# relay-shield.net
KiCad netlist of a schematic drawn in EAGLE
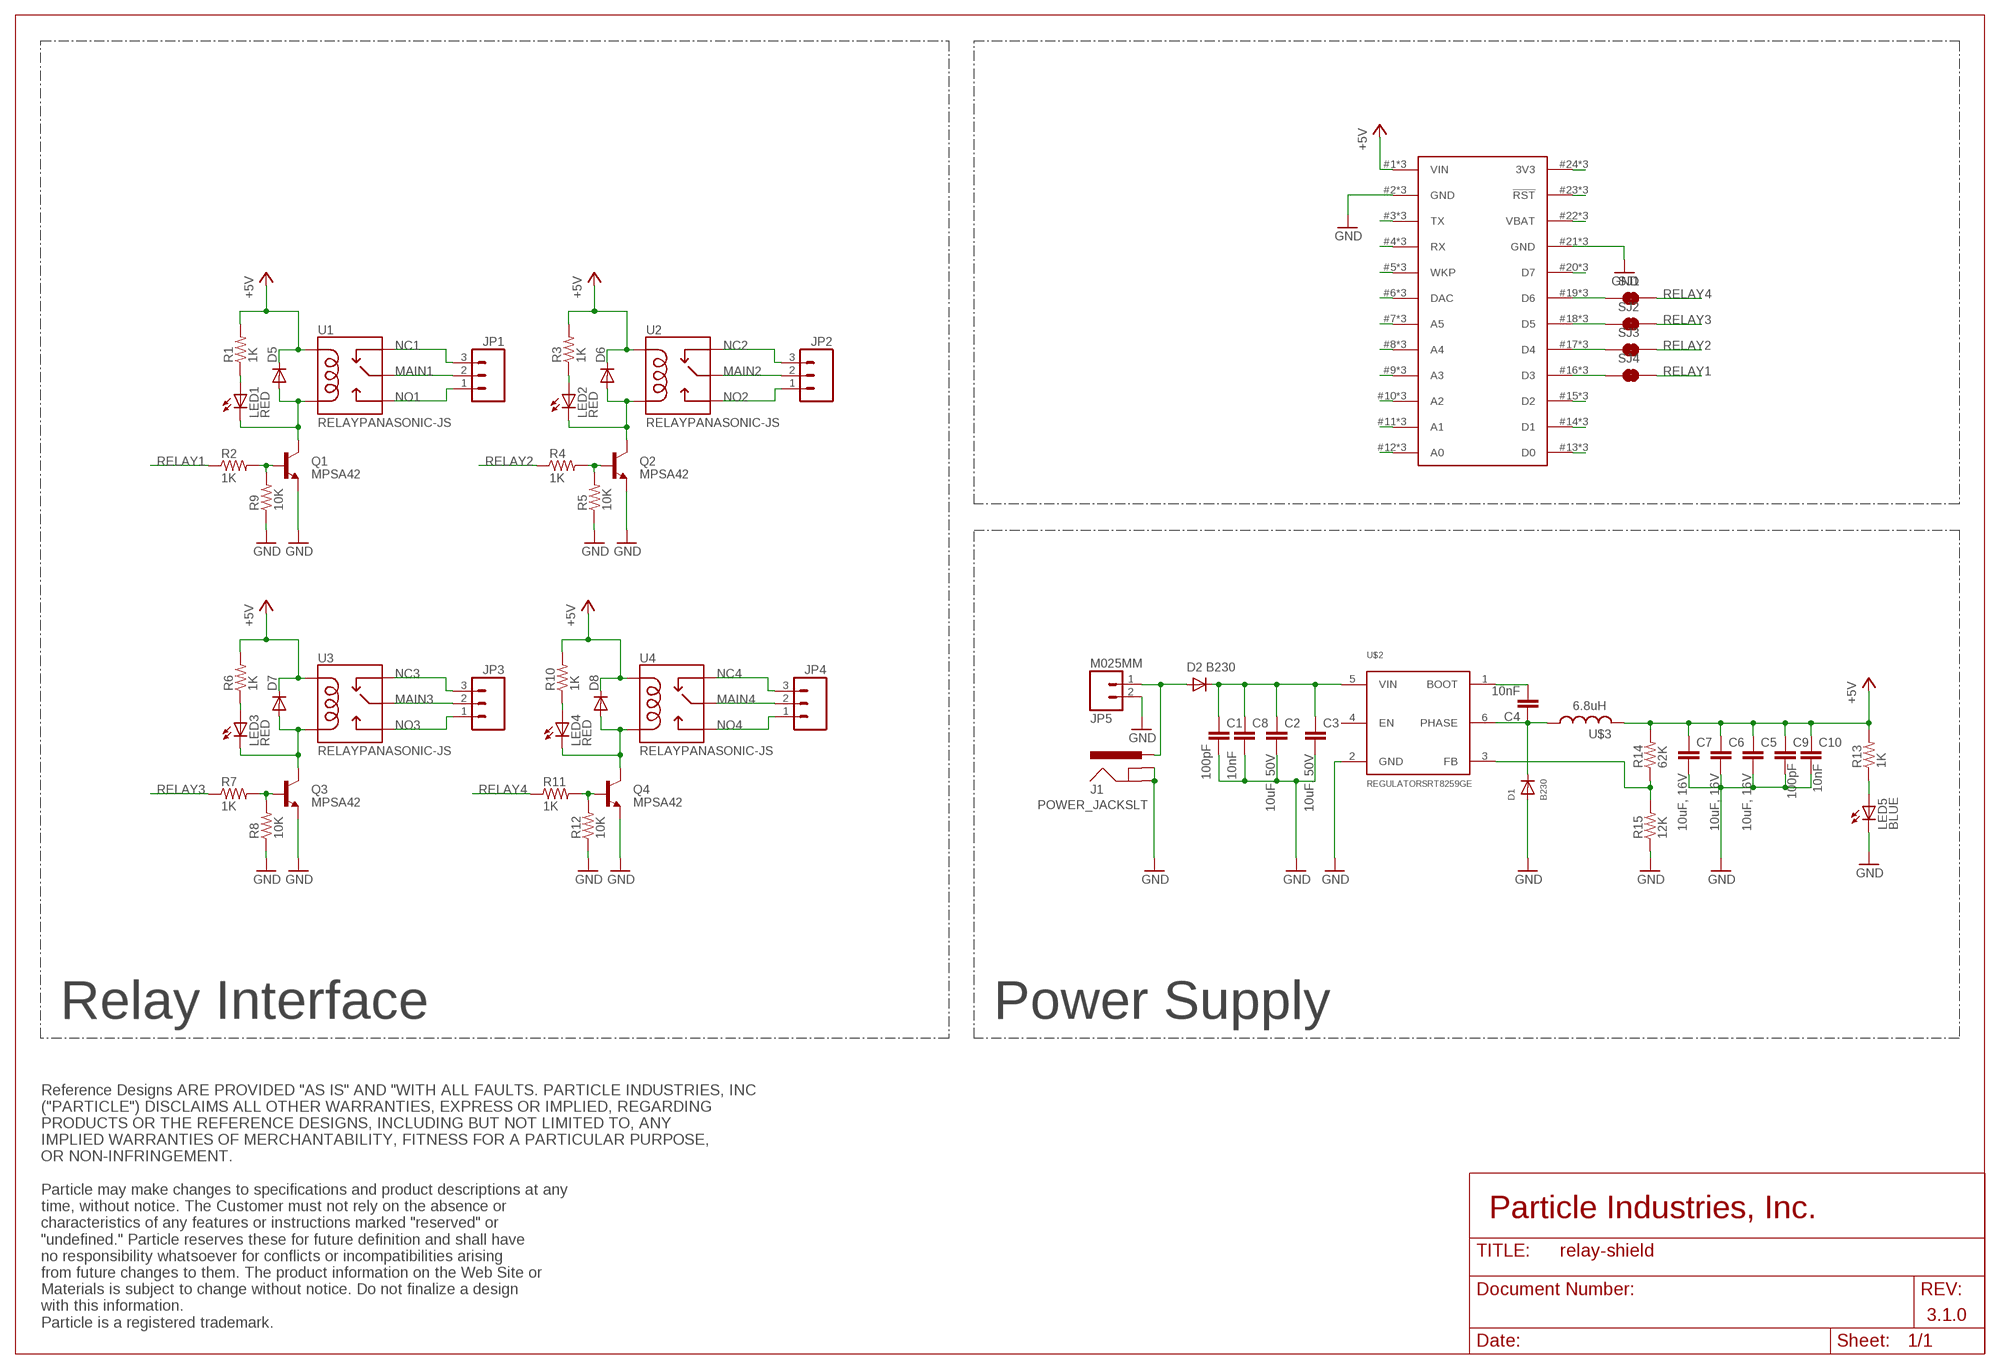
[diagram p0: schematic, sheet 1]

(export (version "E")
  (design (tool "Eeschema 10.0.6"))
  (components
    (comp (ref "C1")
      (value "100pF")
      (footprint "eagle-import:C0603")
      (libsource (lib "eagle-import") (part "C-EUC0603"))
    )
    (comp (ref "C2")
      (value "10uF, 50V")
      (footprint "eagle-import:1206")
      (libsource (lib "eagle-import") (part "CAP1206"))
    )
    (comp (ref "C3")
      (value "10uF, 50V")
      (footprint "eagle-import:1206")
      (libsource (lib "eagle-import") (part "CAP1206"))
    )
    (comp (ref "C4")
      (value "10nF")
      (footprint "eagle-import:0603-CAP")
      (libsource (lib "eagle-import") (part "CAP0603-CAP"))
    )
    (comp (ref "C5")
      (value "10uF, 16V")
      (footprint "eagle-import:1206")
      (libsource (lib "eagle-import") (part "CAP1206"))
    )
    (comp (ref "C6")
      (value "10uF, 16V")
      (footprint "eagle-import:1206")
      (libsource (lib "eagle-import") (part "CAP1206"))
    )
    (comp (ref "C7")
      (value "10uF, 16V")
      (footprint "eagle-import:1206")
      (libsource (lib "eagle-import") (part "CAP1206"))
    )
    (comp (ref "C8")
      (value "10nF")
      (footprint "eagle-import:C0603")
      (libsource (lib "eagle-import") (part "C-EUC0603"))
    )
    (comp (ref "C9")
      (value "100pF")
      (footprint "eagle-import:C0603")
      (libsource (lib "eagle-import") (part "C-EUC0603"))
    )
    (comp (ref "C10")
      (value "10nF")
      (footprint "eagle-import:C0603")
      (libsource (lib "eagle-import") (part "C-EUC0603"))
    )
    (comp (ref "D1")
      (value "B230")
      (footprint "eagle-import:SMADIODE")
      (libsource (lib "eagle-import") (part "DIODESMA"))
    )
    (comp (ref "D2")
      (value "B230")
      (footprint "eagle-import:SMADIODE")
      (libsource (lib "eagle-import") (part "DIODESMA"))
    )
    (comp (ref "D5")
      (value "DIODE-SOD123")
      (footprint "eagle-import:SOD123")
      (libsource (lib "eagle-import") (part "DIODE-SOD123"))
    )
    (comp (ref "D6")
      (value "DIODE-SOD123")
      (footprint "eagle-import:SOD123")
      (libsource (lib "eagle-import") (part "DIODE-SOD123"))
    )
    (comp (ref "D7")
      (value "DIODE-SOD123")
      (footprint "eagle-import:SOD123")
      (libsource (lib "eagle-import") (part "DIODE-SOD123"))
    )
    (comp (ref "D8")
      (value "DIODE-SOD123")
      (footprint "eagle-import:SOD123")
      (libsource (lib "eagle-import") (part "DIODE-SOD123"))
    )
    (comp (ref "J1")
      (value "POWER_JACKSLT")
      (footprint "eagle-import:POWER_JACK_SLOT")
      (libsource (lib "eagle-import") (part "POWER_JACKSLT"))
    )
    (comp (ref "JP1")
      (value "M03-SCREW-5MM")
      (footprint "eagle-import:SCREWTERMINAL-5MM-3")
      (libsource (lib "eagle-import") (part "M03-SCREW-5MM"))
    )
    (comp (ref "JP2")
      (value "M03-SCREW-5MM")
      (footprint "eagle-import:SCREWTERMINAL-5MM-3")
      (libsource (lib "eagle-import") (part "M03-SCREW-5MM"))
    )
    (comp (ref "JP3")
      (value "M03-SCREW-5MM")
      (footprint "eagle-import:SCREWTERMINAL-5MM-3")
      (libsource (lib "eagle-import") (part "M03-SCREW-5MM"))
    )
    (comp (ref "JP4")
      (value "M03-SCREW-5MM")
      (footprint "eagle-import:SCREWTERMINAL-5MM-3")
      (libsource (lib "eagle-import") (part "M03-SCREW-5MM"))
    )
    (comp (ref "JP5")
      (value "M025MM")
      (footprint "eagle-import:SCREWTERMINAL-5MM-2")
      (libsource (lib "eagle-import") (part "M025MM"))
    )
    (comp (ref "LED1")
      (value "RED")
      (footprint "eagle-import:LED-0603")
      (libsource (lib "eagle-import") (part "LED0603"))
    )
    (comp (ref "LED2")
      (value "RED")
      (footprint "eagle-import:LED-0603")
      (libsource (lib "eagle-import") (part "LED0603"))
    )
    (comp (ref "LED3")
      (value "RED")
      (footprint "eagle-import:LED-0603")
      (libsource (lib "eagle-import") (part "LED0603"))
    )
    (comp (ref "LED4")
      (value "RED")
      (footprint "eagle-import:LED-0603")
      (libsource (lib "eagle-import") (part "LED0603"))
    )
    (comp (ref "LED5")
      (value "BLUE")
      (footprint "eagle-import:LED-0603")
      (libsource (lib "eagle-import") (part "LED0603"))
    )
    (comp (ref "Q1")
      (value "MPSA42")
      (footprint "eagle-import:SOT23")
      (libsource (lib "eagle-import") (part "TRANSISTOR_NPNMPSA42"))
    )
    (comp (ref "Q2")
      (value "MPSA42")
      (footprint "eagle-import:SOT23")
      (libsource (lib "eagle-import") (part "TRANSISTOR_NPNMPSA42"))
    )
    (comp (ref "Q3")
      (value "MPSA42")
      (footprint "eagle-import:SOT23")
      (libsource (lib "eagle-import") (part "TRANSISTOR_NPNMPSA42"))
    )
    (comp (ref "Q4")
      (value "MPSA42")
      (footprint "eagle-import:SOT23")
      (libsource (lib "eagle-import") (part "TRANSISTOR_NPNMPSA42"))
    )
    (comp (ref "R1")
      (value "1K")
      (footprint "eagle-import:0603-RES")
      (libsource (lib "eagle-import") (part "RESISTOR0603-RES"))
    )
    (comp (ref "R2")
      (value "1K")
      (footprint "eagle-import:0603-RES")
      (libsource (lib "eagle-import") (part "RESISTOR0603-RES"))
    )
    (comp (ref "R3")
      (value "1K")
      (footprint "eagle-import:0603-RES")
      (libsource (lib "eagle-import") (part "RESISTOR0603-RES"))
    )
    (comp (ref "R4")
      (value "1K")
      (footprint "eagle-import:0603-RES")
      (libsource (lib "eagle-import") (part "RESISTOR0603-RES"))
    )
    (comp (ref "R5")
      (value "10K")
      (footprint "eagle-import:0603-RES")
      (libsource (lib "eagle-import") (part "RESISTOR0603-RES"))
    )
    (comp (ref "R6")
      (value "1K")
      (footprint "eagle-import:0603-RES")
      (libsource (lib "eagle-import") (part "RESISTOR0603-RES"))
    )
    (comp (ref "R7")
      (value "1K")
      (footprint "eagle-import:0603-RES")
      (libsource (lib "eagle-import") (part "RESISTOR0603-RES"))
    )
    (comp (ref "R8")
      (value "10K")
      (footprint "eagle-import:0603-RES")
      (libsource (lib "eagle-import") (part "RESISTOR0603-RES"))
    )
    (comp (ref "R9")
      (value "10K")
      (footprint "eagle-import:0603-RES")
      (libsource (lib "eagle-import") (part "RESISTOR0603-RES"))
    )
    (comp (ref "R10")
      (value "1K")
      (footprint "eagle-import:0603-RES")
      (libsource (lib "eagle-import") (part "RESISTOR0603-RES"))
    )
    (comp (ref "R11")
      (value "1K")
      (footprint "eagle-import:0603-RES")
      (libsource (lib "eagle-import") (part "RESISTOR0603-RES"))
    )
    (comp (ref "R12")
      (value "10K")
      (footprint "eagle-import:0603-RES")
      (libsource (lib "eagle-import") (part "RESISTOR0603-RES"))
    )
    (comp (ref "R13")
      (value "1K")
      (footprint "eagle-import:0603-RES")
      (libsource (lib "eagle-import") (part "RESISTOR0603-RES"))
    )
    (comp (ref "R14")
      (value "62K")
      (footprint "eagle-import:0603-RES")
      (libsource (lib "eagle-import") (part "RESISTOR0603-RES"))
    )
    (comp (ref "R15")
      (value "12K")
      (footprint "eagle-import:0603-RES")
      (libsource (lib "eagle-import") (part "RESISTOR0603-RES"))
    )
    (comp (ref "SJ1")
      (value "JUMPER-PAD-2-NC_BY_TRACE")
      (footprint "eagle-import:PAD-JUMPER-2-NC_BY_TRACE_YES_SILK")
      (libsource (lib "eagle-import") (part "JUMPER-PAD-2-NC_BY_TRACE"))
    )
    (comp (ref "SJ2")
      (value "JUMPER-PAD-2-NC_BY_TRACE")
      (footprint "eagle-import:PAD-JUMPER-2-NC_BY_TRACE_YES_SILK")
      (libsource (lib "eagle-import") (part "JUMPER-PAD-2-NC_BY_TRACE"))
    )
    (comp (ref "SJ3")
      (value "JUMPER-PAD-2-NC_BY_TRACE")
      (footprint "eagle-import:PAD-JUMPER-2-NC_BY_TRACE_YES_SILK")
      (libsource (lib "eagle-import") (part "JUMPER-PAD-2-NC_BY_TRACE"))
    )
    (comp (ref "SJ4")
      (value "JUMPER-PAD-2-NC_BY_TRACE")
      (footprint "eagle-import:PAD-JUMPER-2-NC_BY_TRACE_YES_SILK")
      (libsource (lib "eagle-import") (part "JUMPER-PAD-2-NC_BY_TRACE"))
    )
    (comp (ref "U$1")
      (value "SPARK_CORESTACKABLE")
      (footprint "eagle-import:SPARK_CORE_STACKABLE")
      (libsource (lib "eagle-import") (part "SPARK_CORESTACKABLE"))
    )
    (comp (ref "U$2")
      (value "REGULATORSRT8259GE")
      (footprint "eagle-import:SOT23-6")
      (libsource (lib "eagle-import") (part "REGULATORSRT8259GE"))
    )
    (comp (ref "U$3")
      (value "INDUCTORS")
      (footprint "eagle-import:NR8040T6R8N")
      (libsource (lib "eagle-import") (part "INDUCTORS"))
    )
    (comp (ref "U1")
      (value "RELAYPANASONIC-JS")
      (footprint "eagle-import:JS1-5V-F")
      (libsource (lib "eagle-import") (part "RELAYPANASONIC-JS"))
    )
    (comp (ref "U2")
      (value "RELAYPANASONIC-JS")
      (footprint "eagle-import:JS1-5V-F")
      (libsource (lib "eagle-import") (part "RELAYPANASONIC-JS"))
    )
    (comp (ref "U3")
      (value "RELAYPANASONIC-JS")
      (footprint "eagle-import:JS1-5V-F")
      (libsource (lib "eagle-import") (part "RELAYPANASONIC-JS"))
    )
    (comp (ref "U4")
      (value "RELAYPANASONIC-JS")
      (footprint "eagle-import:JS1-5V-F")
      (libsource (lib "eagle-import") (part "RELAYPANASONIC-JS"))
    )
  )
  (nets
    (net (code "1") (name "+5V") (class "Default")
      (node (ref "C10") (pin "1") (pinfunction "1_1") (pintype "passive"))
      (node (ref "C5") (pin "1") (pinfunction "1_1") (pintype "passive"))
      (node (ref "C6") (pin "1") (pinfunction "1_1") (pintype "passive"))
      (node (ref "C7") (pin "1") (pinfunction "1_1") (pintype "passive"))
      (node (ref "C9") (pin "1") (pinfunction "1_1") (pintype "passive"))
      (node (ref "D5") (pin "C") (pinfunction "C_C") (pintype "passive"))
      (node (ref "D6") (pin "C") (pinfunction "C_C") (pintype "passive"))
      (node (ref "D7") (pin "C") (pinfunction "C_C") (pintype "passive"))
      (node (ref "D8") (pin "C") (pinfunction "C_C") (pintype "passive"))
      (node (ref "R1") (pin "2") (pinfunction "2_2") (pintype "passive"))
      (node (ref "R10") (pin "2") (pinfunction "2_2") (pintype "passive"))
      (node (ref "R13") (pin "2") (pinfunction "2_2") (pintype "passive"))
      (node (ref "R14") (pin "2") (pinfunction "2_2") (pintype "passive"))
      (node (ref "R3") (pin "2") (pinfunction "2_2") (pintype "passive"))
      (node (ref "R6") (pin "2") (pinfunction "2_2") (pintype "passive"))
      (node (ref "U$1") (pin "#1") (pinfunction "VIN_#1") (pintype "power_in"))
      (node (ref "U$1") (pin "1") (pinfunction "VIN_1") (pintype "power_in"))
      (node (ref "U$1") (pin "@1") (pinfunction "VIN_@1") (pintype "power_in"))
      (node (ref "U$3") (pin "P$2") (pinfunction "2_P$2") (pintype "passive"))
      (node (ref "U1") (pin "COIL1") (pinfunction "COIL1_COIL1") (pintype "bidirectional"))
      (node (ref "U2") (pin "COIL1") (pinfunction "COIL1_COIL1") (pintype "bidirectional"))
      (node (ref "U3") (pin "COIL1") (pinfunction "COIL1_COIL1") (pintype "bidirectional"))
      (node (ref "U4") (pin "COIL1") (pinfunction "COIL1_COIL1") (pintype "bidirectional"))
    )
    (net (code "2") (name "/MAIN1") (class "Default")
      (node (ref "JP1") (pin "2") (pinfunction "2_2") (pintype "passive"))
      (node (ref "U1") (pin "COMMON") (pinfunction "MAIN_COMMON") (pintype "bidirectional"))
    )
    (net (code "3") (name "/MAIN2") (class "Default")
      (node (ref "JP2") (pin "2") (pinfunction "2_2") (pintype "passive"))
      (node (ref "U2") (pin "COMMON") (pinfunction "MAIN_COMMON") (pintype "bidirectional"))
    )
    (net (code "4") (name "/MAIN3") (class "Default")
      (node (ref "JP3") (pin "2") (pinfunction "2_2") (pintype "passive"))
      (node (ref "U3") (pin "COMMON") (pinfunction "MAIN_COMMON") (pintype "bidirectional"))
    )
    (net (code "5") (name "/MAIN4") (class "Default")
      (node (ref "JP4") (pin "2") (pinfunction "2_2") (pintype "passive"))
      (node (ref "U4") (pin "COMMON") (pinfunction "MAIN_COMMON") (pintype "bidirectional"))
    )
    (net (code "6") (name "/NC1") (class "Default")
      (node (ref "JP1") (pin "3") (pinfunction "3_3") (pintype "passive"))
      (node (ref "U1") (pin "CLOSED") (pinfunction "NC_CLOSED") (pintype "bidirectional"))
    )
    (net (code "7") (name "/NC2") (class "Default")
      (node (ref "JP2") (pin "3") (pinfunction "3_3") (pintype "passive"))
      (node (ref "U2") (pin "CLOSED") (pinfunction "NC_CLOSED") (pintype "bidirectional"))
    )
    (net (code "8") (name "/NC3") (class "Default")
      (node (ref "JP3") (pin "3") (pinfunction "3_3") (pintype "passive"))
      (node (ref "U3") (pin "CLOSED") (pinfunction "NC_CLOSED") (pintype "bidirectional"))
    )
    (net (code "9") (name "/NC4") (class "Default")
      (node (ref "JP4") (pin "3") (pinfunction "3_3") (pintype "passive"))
      (node (ref "U4") (pin "CLOSED") (pinfunction "NC_CLOSED") (pintype "bidirectional"))
    )
    (net (code "10") (name "/NO1") (class "Default")
      (node (ref "JP1") (pin "1") (pinfunction "1_1") (pintype "passive"))
      (node (ref "U1") (pin "OPEN") (pinfunction "NO_OPEN") (pintype "bidirectional"))
    )
    (net (code "11") (name "/NO2") (class "Default")
      (node (ref "JP2") (pin "1") (pinfunction "1_1") (pintype "passive"))
      (node (ref "U2") (pin "OPEN") (pinfunction "NO_OPEN") (pintype "bidirectional"))
    )
    (net (code "12") (name "/NO3") (class "Default")
      (node (ref "JP3") (pin "1") (pinfunction "1_1") (pintype "passive"))
      (node (ref "U3") (pin "OPEN") (pinfunction "NO_OPEN") (pintype "bidirectional"))
    )
    (net (code "13") (name "/NO4") (class "Default")
      (node (ref "JP4") (pin "1") (pinfunction "1_1") (pintype "passive"))
      (node (ref "U4") (pin "OPEN") (pinfunction "NO_OPEN") (pintype "bidirectional"))
    )
    (net (code "14") (name "/RELAY1") (class "Default")
      (node (ref "R2") (pin "1") (pinfunction "1_1") (pintype "passive"))
      (node (ref "SJ4") (pin "2") (pinfunction "2_2") (pintype "passive"))
    )
    (net (code "15") (name "/RELAY2") (class "Default")
      (node (ref "R4") (pin "1") (pinfunction "1_1") (pintype "passive"))
      (node (ref "SJ3") (pin "2") (pinfunction "2_2") (pintype "passive"))
    )
    (net (code "16") (name "/RELAY3") (class "Default")
      (node (ref "R7") (pin "1") (pinfunction "1_1") (pintype "passive"))
      (node (ref "SJ2") (pin "2") (pinfunction "2_2") (pintype "passive"))
    )
    (net (code "17") (name "/RELAY4") (class "Default")
      (node (ref "R11") (pin "1") (pinfunction "1_1") (pintype "passive"))
      (node (ref "SJ1") (pin "2") (pinfunction "2_2") (pintype "passive"))
    )
    (net (code "18") (name "GND") (class "Default")
      (node (ref "C1") (pin "2") (pinfunction "2_2") (pintype "passive"))
      (node (ref "C10") (pin "2") (pinfunction "2_2") (pintype "passive"))
      (node (ref "C2") (pin "2") (pinfunction "2_2") (pintype "passive"))
      (node (ref "C3") (pin "2") (pinfunction "2_2") (pintype "passive"))
      (node (ref "C5") (pin "2") (pinfunction "2_2") (pintype "passive"))
      (node (ref "C6") (pin "2") (pinfunction "2_2") (pintype "passive"))
      (node (ref "C7") (pin "2") (pinfunction "2_2") (pintype "passive"))
      (node (ref "C8") (pin "2") (pinfunction "2_2") (pintype "passive"))
      (node (ref "C9") (pin "2") (pinfunction "2_2") (pintype "passive"))
      (node (ref "D1") (pin "A") (pinfunction "A_A") (pintype "passive"))
      (node (ref "J1") (pin "GND@1") (pinfunction "GNDBREAK_GND@1") (pintype "bidirectional"))
      (node (ref "J1") (pin "GND@2") (pinfunction "GND_GND@2") (pintype "bidirectional"))
      (node (ref "JP5") (pin "2") (pinfunction "2_2") (pintype "passive"))
      (node (ref "LED5") (pin "C") (pinfunction "C_C") (pintype "passive"))
      (node (ref "Q1") (pin "2") (pinfunction "E_2") (pintype "passive"))
      (node (ref "Q2") (pin "2") (pinfunction "E_2") (pintype "passive"))
      (node (ref "Q3") (pin "2") (pinfunction "E_2") (pintype "passive"))
      (node (ref "Q4") (pin "2") (pinfunction "E_2") (pintype "passive"))
      (node (ref "R12") (pin "1") (pinfunction "1_1") (pintype "passive"))
      (node (ref "R15") (pin "1") (pinfunction "1_1") (pintype "passive"))
      (node (ref "R5") (pin "1") (pinfunction "1_1") (pintype "passive"))
      (node (ref "R8") (pin "1") (pinfunction "1_1") (pintype "passive"))
      (node (ref "R9") (pin "1") (pinfunction "1_1") (pintype "passive"))
      (node (ref "U$1") (pin "#2") (pinfunction "GND_#2") (pintype "power_in"))
      (node (ref "U$1") (pin "#21") (pinfunction "GND_#21") (pintype "power_in"))
      (node (ref "U$1") (pin "2") (pinfunction "GND_2") (pintype "power_in"))
      (node (ref "U$1") (pin "21") (pinfunction "GND_21") (pintype "power_in"))
      (node (ref "U$1") (pin "@2") (pinfunction "GND_@2") (pintype "power_in"))
      (node (ref "U$1") (pin "@21") (pinfunction "GND_@21") (pintype "power_in"))
      (node (ref "U$2") (pin "2") (pinfunction "GND_2") (pintype "bidirectional"))
    )
    (net (code "19") (name "Net-(D2-PadA)") (class "Default")
      (node (ref "D2") (pin "A") (pinfunction "A_A") (pintype "passive"))
      (node (ref "J1") (pin "PWR") (pinfunction "PWR_PWR") (pintype "bidirectional"))
      (node (ref "JP5") (pin "1") (pinfunction "1_1") (pintype "passive"))
    )
    (net (code "20") (name "Net-(LED1-PadA)") (class "Default")
      (node (ref "LED1") (pin "A") (pinfunction "A_A") (pintype "passive"))
      (node (ref "R1") (pin "1") (pinfunction "1_1") (pintype "passive"))
    )
    (net (code "21") (name "Net-(LED2-PadA)") (class "Default")
      (node (ref "LED2") (pin "A") (pinfunction "A_A") (pintype "passive"))
      (node (ref "R3") (pin "1") (pinfunction "1_1") (pintype "passive"))
    )
    (net (code "22") (name "Net-(LED3-PadA)") (class "Default")
      (node (ref "LED3") (pin "A") (pinfunction "A_A") (pintype "passive"))
      (node (ref "R6") (pin "1") (pinfunction "1_1") (pintype "passive"))
    )
    (net (code "23") (name "Net-(LED4-PadA)") (class "Default")
      (node (ref "LED4") (pin "A") (pinfunction "A_A") (pintype "passive"))
      (node (ref "R10") (pin "1") (pinfunction "1_1") (pintype "passive"))
    )
    (net (code "24") (name "Net-(LED5-PadA)") (class "Default")
      (node (ref "LED5") (pin "A") (pinfunction "A_A") (pintype "passive"))
      (node (ref "R13") (pin "1") (pinfunction "1_1") (pintype "passive"))
    )
    (net (code "25") (name "Net-(Q1-B)") (class "Default")
      (node (ref "Q1") (pin "1") (pinfunction "B_1") (pintype "passive"))
      (node (ref "R2") (pin "2") (pinfunction "2_2") (pintype "passive"))
      (node (ref "R9") (pin "2") (pinfunction "2_2") (pintype "passive"))
    )
    (net (code "26") (name "Net-(Q1-C)") (class "Default")
      (node (ref "D5") (pin "A") (pinfunction "A_A") (pintype "passive"))
      (node (ref "LED1") (pin "C") (pinfunction "C_C") (pintype "passive"))
      (node (ref "Q1") (pin "3") (pinfunction "C_3") (pintype "passive"))
      (node (ref "U1") (pin "COIL2") (pinfunction "COIL2_COIL2") (pintype "bidirectional"))
    )
    (net (code "27") (name "Net-(Q2-B)") (class "Default")
      (node (ref "Q2") (pin "1") (pinfunction "B_1") (pintype "passive"))
      (node (ref "R4") (pin "2") (pinfunction "2_2") (pintype "passive"))
      (node (ref "R5") (pin "2") (pinfunction "2_2") (pintype "passive"))
    )
    (net (code "28") (name "Net-(Q2-C)") (class "Default")
      (node (ref "D6") (pin "A") (pinfunction "A_A") (pintype "passive"))
      (node (ref "LED2") (pin "C") (pinfunction "C_C") (pintype "passive"))
      (node (ref "Q2") (pin "3") (pinfunction "C_3") (pintype "passive"))
      (node (ref "U2") (pin "COIL2") (pinfunction "COIL2_COIL2") (pintype "bidirectional"))
    )
    (net (code "29") (name "Net-(Q3-B)") (class "Default")
      (node (ref "Q3") (pin "1") (pinfunction "B_1") (pintype "passive"))
      (node (ref "R7") (pin "2") (pinfunction "2_2") (pintype "passive"))
      (node (ref "R8") (pin "2") (pinfunction "2_2") (pintype "passive"))
    )
    (net (code "30") (name "Net-(Q3-C)") (class "Default")
      (node (ref "D7") (pin "A") (pinfunction "A_A") (pintype "passive"))
      (node (ref "LED3") (pin "C") (pinfunction "C_C") (pintype "passive"))
      (node (ref "Q3") (pin "3") (pinfunction "C_3") (pintype "passive"))
      (node (ref "U3") (pin "COIL2") (pinfunction "COIL2_COIL2") (pintype "bidirectional"))
    )
    (net (code "31") (name "Net-(Q4-B)") (class "Default")
      (node (ref "Q4") (pin "1") (pinfunction "B_1") (pintype "passive"))
      (node (ref "R11") (pin "2") (pinfunction "2_2") (pintype "passive"))
      (node (ref "R12") (pin "2") (pinfunction "2_2") (pintype "passive"))
    )
    (net (code "32") (name "Net-(Q4-C)") (class "Default")
      (node (ref "D8") (pin "A") (pinfunction "A_A") (pintype "passive"))
      (node (ref "LED4") (pin "C") (pinfunction "C_C") (pintype "passive"))
      (node (ref "Q4") (pin "3") (pinfunction "C_3") (pintype "passive"))
      (node (ref "U4") (pin "COIL2") (pinfunction "COIL2_COIL2") (pintype "bidirectional"))
    )
    (net (code "33") (name "Net-(SJ1-Pad1)") (class "Default")
      (node (ref "SJ1") (pin "1") (pinfunction "1_1") (pintype "passive"))
      (node (ref "U$1") (pin "#19") (pinfunction "D6_#19") (pintype "bidirectional"))
      (node (ref "U$1") (pin "19") (pinfunction "D6_19") (pintype "bidirectional"))
      (node (ref "U$1") (pin "@19") (pinfunction "D6_@19") (pintype "bidirectional"))
    )
    (net (code "34") (name "Net-(SJ2-Pad1)") (class "Default")
      (node (ref "SJ2") (pin "1") (pinfunction "1_1") (pintype "passive"))
      (node (ref "U$1") (pin "#18") (pinfunction "D5_#18") (pintype "bidirectional"))
      (node (ref "U$1") (pin "18") (pinfunction "D5_18") (pintype "bidirectional"))
      (node (ref "U$1") (pin "@18") (pinfunction "D5_@18") (pintype "bidirectional"))
    )
    (net (code "35") (name "Net-(SJ3-Pad1)") (class "Default")
      (node (ref "SJ3") (pin "1") (pinfunction "1_1") (pintype "passive"))
      (node (ref "U$1") (pin "#17") (pinfunction "D4_#17") (pintype "bidirectional"))
      (node (ref "U$1") (pin "17") (pinfunction "D4_17") (pintype "bidirectional"))
      (node (ref "U$1") (pin "@17") (pinfunction "D4_@17") (pintype "bidirectional"))
    )
    (net (code "36") (name "Net-(SJ4-Pad1)") (class "Default")
      (node (ref "SJ4") (pin "1") (pinfunction "1_1") (pintype "passive"))
      (node (ref "U$1") (pin "#16") (pinfunction "D3_#16") (pintype "bidirectional"))
      (node (ref "U$1") (pin "16") (pinfunction "D3_16") (pintype "bidirectional"))
      (node (ref "U$1") (pin "@16") (pinfunction "D3_@16") (pintype "bidirectional"))
    )
    (net (code "37") (name "Net-(U$1-3V3-Pad#24)") (class "Default")
      (node (ref "U$1") (pin "#24") (pinfunction "3V3_#24") (pintype "power_in"))
      (node (ref "U$1") (pin "24") (pinfunction "3V3_24") (pintype "power_in"))
      (node (ref "U$1") (pin "@24") (pinfunction "3V3_@24") (pintype "power_in"))
    )
    (net (code "38") (name "Net-(U$1-A0-Pad#12)") (class "Default")
      (node (ref "U$1") (pin "#12") (pinfunction "A0_#12") (pintype "bidirectional"))
      (node (ref "U$1") (pin "12") (pinfunction "A0_12") (pintype "bidirectional"))
      (node (ref "U$1") (pin "@12") (pinfunction "A0_@12") (pintype "bidirectional"))
    )
    (net (code "39") (name "Net-(U$1-A1-Pad#11)") (class "Default")
      (node (ref "U$1") (pin "#11") (pinfunction "A1_#11") (pintype "bidirectional"))
      (node (ref "U$1") (pin "11") (pinfunction "A1_11") (pintype "bidirectional"))
      (node (ref "U$1") (pin "@11") (pinfunction "A1_@11") (pintype "bidirectional"))
    )
    (net (code "40") (name "Net-(U$1-A2-Pad#10)") (class "Default")
      (node (ref "U$1") (pin "#10") (pinfunction "A2_#10") (pintype "bidirectional"))
      (node (ref "U$1") (pin "10") (pinfunction "A2_10") (pintype "bidirectional"))
      (node (ref "U$1") (pin "@10") (pinfunction "A2_@10") (pintype "bidirectional"))
    )
    (net (code "41") (name "Net-(U$1-A3-Pad#9)") (class "Default")
      (node (ref "U$1") (pin "#9") (pinfunction "A3_#9") (pintype "bidirectional"))
      (node (ref "U$1") (pin "9") (pinfunction "A3_9") (pintype "bidirectional"))
      (node (ref "U$1") (pin "@9") (pinfunction "A3_@9") (pintype "bidirectional"))
    )
    (net (code "42") (name "Net-(U$1-A4-Pad#8)") (class "Default")
      (node (ref "U$1") (pin "#8") (pinfunction "A4_#8") (pintype "bidirectional"))
      (node (ref "U$1") (pin "8") (pinfunction "A4_8") (pintype "bidirectional"))
      (node (ref "U$1") (pin "@8") (pinfunction "A4_@8") (pintype "bidirectional"))
    )
    (net (code "43") (name "Net-(U$1-A5-Pad#7)") (class "Default")
      (node (ref "U$1") (pin "#7") (pinfunction "A5_#7") (pintype "bidirectional"))
      (node (ref "U$1") (pin "7") (pinfunction "A5_7") (pintype "bidirectional"))
      (node (ref "U$1") (pin "@7") (pinfunction "A5_@7") (pintype "bidirectional"))
    )
    (net (code "44") (name "Net-(U$1-D0-Pad#13)") (class "Default")
      (node (ref "U$1") (pin "#13") (pinfunction "D0_#13") (pintype "bidirectional"))
      (node (ref "U$1") (pin "13") (pinfunction "D0_13") (pintype "bidirectional"))
      (node (ref "U$1") (pin "@13") (pinfunction "D0_@13") (pintype "bidirectional"))
    )
    (net (code "45") (name "Net-(U$1-D1-Pad#14)") (class "Default")
      (node (ref "U$1") (pin "#14") (pinfunction "D1_#14") (pintype "bidirectional"))
      (node (ref "U$1") (pin "14") (pinfunction "D1_14") (pintype "bidirectional"))
      (node (ref "U$1") (pin "@14") (pinfunction "D1_@14") (pintype "bidirectional"))
    )
    (net (code "46") (name "Net-(U$1-D2-Pad#15)") (class "Default")
      (node (ref "U$1") (pin "#15") (pinfunction "D2_#15") (pintype "bidirectional"))
      (node (ref "U$1") (pin "15") (pinfunction "D2_15") (pintype "bidirectional"))
      (node (ref "U$1") (pin "@15") (pinfunction "D2_@15") (pintype "bidirectional"))
    )
    (net (code "47") (name "Net-(U$1-D7-Pad#20)") (class "Default")
      (node (ref "U$1") (pin "#20") (pinfunction "D7_#20") (pintype "bidirectional"))
      (node (ref "U$1") (pin "20") (pinfunction "D7_20") (pintype "bidirectional"))
      (node (ref "U$1") (pin "@20") (pinfunction "D7_@20") (pintype "bidirectional"))
    )
    (net (code "48") (name "Net-(U$1-DAC-Pad#6)") (class "Default")
      (node (ref "U$1") (pin "#6") (pinfunction "DAC_#6") (pintype "bidirectional"))
      (node (ref "U$1") (pin "6") (pinfunction "DAC_6") (pintype "bidirectional"))
      (node (ref "U$1") (pin "@6") (pinfunction "DAC_@6") (pintype "bidirectional"))
    )
    (net (code "49") (name "Net-(U$1-RX-Pad#4)") (class "Default")
      (node (ref "U$1") (pin "#4") (pinfunction "RX_#4") (pintype "bidirectional"))
      (node (ref "U$1") (pin "4") (pinfunction "RX_4") (pintype "bidirectional"))
      (node (ref "U$1") (pin "@4") (pinfunction "RX_@4") (pintype "bidirectional"))
    )
    (net (code "50") (name "Net-(U$1-TX-Pad#3)") (class "Default")
      (node (ref "U$1") (pin "#3") (pinfunction "TX_#3") (pintype "bidirectional"))
      (node (ref "U$1") (pin "3") (pinfunction "TX_3") (pintype "bidirectional"))
      (node (ref "U$1") (pin "@3") (pinfunction "TX_@3") (pintype "bidirectional"))
    )
    (net (code "51") (name "Net-(U$1-VBAT-Pad#22)") (class "Default")
      (node (ref "U$1") (pin "#22") (pinfunction "VBAT_#22") (pintype "power_in"))
      (node (ref "U$1") (pin "22") (pinfunction "VBAT_22") (pintype "power_in"))
      (node (ref "U$1") (pin "@22") (pinfunction "VBAT_@22") (pintype "power_in"))
    )
    (net (code "52") (name "Net-(U$1-WKP-Pad#5)") (class "Default")
      (node (ref "U$1") (pin "#5") (pinfunction "WKP_#5") (pintype "bidirectional"))
      (node (ref "U$1") (pin "5") (pinfunction "WKP_5") (pintype "bidirectional"))
      (node (ref "U$1") (pin "@5") (pinfunction "WKP_@5") (pintype "bidirectional"))
    )
    (net (code "53") (name "Net-(U$1-~{RST}-Pad#23)") (class "Default")
      (node (ref "U$1") (pin "#23") (pinfunction "~{RST}_#23") (pintype "bidirectional"))
      (node (ref "U$1") (pin "23") (pinfunction "~{RST}_23") (pintype "bidirectional"))
      (node (ref "U$1") (pin "@23") (pinfunction "~{RST}_@23") (pintype "bidirectional"))
    )
    (net (code "54") (name "Net-(U$2-BOOT)") (class "Default")
      (node (ref "C4") (pin "2") (pinfunction "2_2") (pintype "passive"))
      (node (ref "U$2") (pin "1") (pinfunction "BOOT_1") (pintype "power_in"))
    )
    (net (code "55") (name "Net-(U$2-FB)") (class "Default")
      (node (ref "R14") (pin "1") (pinfunction "1_1") (pintype "passive"))
      (node (ref "R15") (pin "2") (pinfunction "2_2") (pintype "passive"))
      (node (ref "U$2") (pin "3") (pinfunction "FB_3") (pintype "input"))
    )
    (net (code "56") (name "Net-(U$2-PHASE)") (class "Default")
      (node (ref "C4") (pin "1") (pinfunction "1_1") (pintype "passive"))
      (node (ref "D1") (pin "C") (pinfunction "C_C") (pintype "passive"))
      (node (ref "U$2") (pin "6") (pinfunction "PHASE_6") (pintype "output"))
      (node (ref "U$3") (pin "P$1") (pinfunction "1_P$1") (pintype "passive"))
    )
    (net (code "57") (name "Net-(U$2-VIN)") (class "Default")
      (node (ref "C1") (pin "1") (pinfunction "1_1") (pintype "passive"))
      (node (ref "C2") (pin "1") (pinfunction "1_1") (pintype "passive"))
      (node (ref "C3") (pin "1") (pinfunction "1_1") (pintype "passive"))
      (node (ref "C8") (pin "1") (pinfunction "1_1") (pintype "passive"))
      (node (ref "D2") (pin "C") (pinfunction "C_C") (pintype "passive"))
      (node (ref "U$2") (pin "5") (pinfunction "VIN_5") (pintype "power_in"))
    )
    (net (code "58") (name "unconnected-(U$2-EN-Pad4)") (class "Default")
      (node (ref "U$2") (pin "4") (pinfunction "EN_4") (pintype "input"))
    )
  )
)
